# 3PDT_2FX.net
KiCad netlist of a schematic drawn in EAGLE
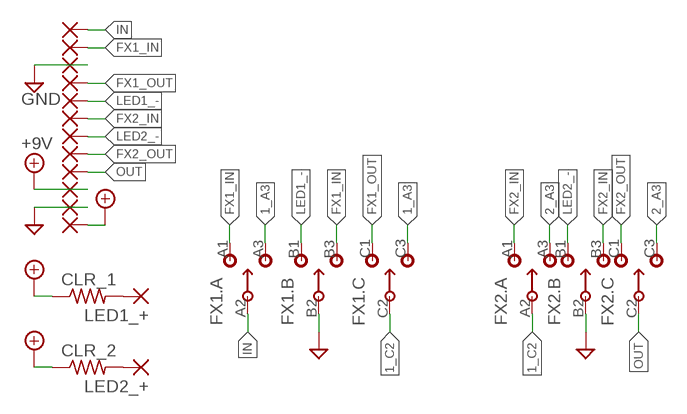
[diagram p0: schematic, sheet 1]

(export (version "E")
  (design (tool "Eeschema 10.0.6"))
  (components
    (comp (ref "+9V")
      (value "1,6/0,8")
      (footprint "eagle-import:1,6_0,8")
      (libsource (lib "eagle-import") (part "1,6/0,8"))
    )
    (comp (ref "+9V1")
      (value "1,6/0,8")
      (footprint "eagle-import:1,6_0,8")
      (libsource (lib "eagle-import") (part "1,6/0,8"))
    )
    (comp (ref "CLR_1")
      (value "R-US_R0603")
      (footprint "eagle-import:R0603")
      (libsource (lib "eagle-import") (part "R-US_R0603"))
    )
    (comp (ref "CLR_2")
      (value "R-US_R0603")
      (footprint "eagle-import:R0603")
      (libsource (lib "eagle-import") (part "R-US_R0603"))
    )
    (comp (ref "FX1")
      (value "3PDT.LUGS")
      (footprint "eagle-import:3PDT.LUGS")
      (libsource (lib "eagle-import") (part "3PDT.LUGS"))
    )
    (comp (ref "FX1_IN")
      (value "1,6/0,8")
      (footprint "eagle-import:1,6_0,8")
      (libsource (lib "eagle-import") (part "1,6/0,8"))
    )
    (comp (ref "FX1_OUT")
      (value "1,6/0,8")
      (footprint "eagle-import:1,6_0,8")
      (libsource (lib "eagle-import") (part "1,6/0,8"))
    )
    (comp (ref "FX2")
      (value "3PDT.LUGS")
      (footprint "eagle-import:3PDT.LUGS")
      (libsource (lib "eagle-import") (part "3PDT.LUGS"))
    )
    (comp (ref "FX2_IN")
      (value "1,6/0,8")
      (footprint "eagle-import:1,6_0,8")
      (libsource (lib "eagle-import") (part "1,6/0,8"))
    )
    (comp (ref "FX2_OUT")
      (value "1,6/0,8")
      (footprint "eagle-import:1,6_0,8")
      (libsource (lib "eagle-import") (part "1,6/0,8"))
    )
    (comp (ref "GND")
      (value "1,6/0,8")
      (footprint "eagle-import:1,6_0,8")
      (libsource (lib "eagle-import") (part "1,6/0,8"))
    )
    (comp (ref "IN")
      (value "1,6/0,8")
      (footprint "eagle-import:1,6_0,8")
      (libsource (lib "eagle-import") (part "1,6/0,8"))
    )
    (comp (ref "LED1_+")
      (value "1,6/0,8")
      (footprint "eagle-import:1,6_0,8")
      (libsource (lib "eagle-import") (part "1,6/0,8"))
    )
    (comp (ref "LED1_-")
      (value "1,6/0,8")
      (footprint "eagle-import:1,6_0,8")
      (libsource (lib "eagle-import") (part "1,6/0,8"))
    )
    (comp (ref "LED2_+")
      (value "1,6/0,8")
      (footprint "eagle-import:1,6_0,8")
      (libsource (lib "eagle-import") (part "1,6/0,8"))
    )
    (comp (ref "LED2_-")
      (value "1,6/0,8")
      (footprint "eagle-import:1,6_0,8")
      (libsource (lib "eagle-import") (part "1,6/0,8"))
    )
    (comp (ref "OUT")
      (value "1,6/0,8")
      (footprint "eagle-import:1,6_0,8")
      (libsource (lib "eagle-import") (part "1,6/0,8"))
    )
    (comp (ref "PAD3")
      (value "1,6/0,8")
      (footprint "eagle-import:1,6_0,8")
      (libsource (lib "eagle-import") (part "1,6/0,8"))
    )
  )
  (nets
    (net (code "1") (name "+9V") (class "Default")
      (node (ref "+9V") (pin "1") (pinfunction "P_1") (pintype "passive"))
      (node (ref "+9V1") (pin "1") (pinfunction "P_1") (pintype "passive"))
      (node (ref "CLR_1") (pin "1") (pinfunction "1_1") (pintype "passive"))
      (node (ref "CLR_2") (pin "1") (pinfunction "1_1") (pintype "passive"))
    )
    (net (code "2") (name "1_A3") (class "Default")
      (node (ref "FX1") (pin "A3") (pinfunction "3_A3") (pintype "passive"))
      (node (ref "FX1") (pin "C3") (pinfunction "3_C3") (pintype "passive"))
    )
    (net (code "3") (name "1_C2") (class "Default")
      (node (ref "FX1") (pin "C2") (pinfunction "2_C2") (pintype "passive"))
      (node (ref "FX2") (pin "A2") (pinfunction "2_A2") (pintype "passive"))
    )
    (net (code "4") (name "2_A3") (class "Default")
      (node (ref "FX2") (pin "A3") (pinfunction "3_A3") (pintype "passive"))
      (node (ref "FX2") (pin "C3") (pinfunction "3_C3") (pintype "passive"))
    )
    (net (code "5") (name "FX1_IN") (class "Default")
      (node (ref "FX1") (pin "A1") (pinfunction "1_A1") (pintype "passive"))
      (node (ref "FX1") (pin "B3") (pinfunction "3_B3") (pintype "passive"))
      (node (ref "FX1_IN") (pin "1") (pinfunction "P_1") (pintype "passive"))
    )
    (net (code "6") (name "FX1_OUT") (class "Default")
      (node (ref "FX1") (pin "C1") (pinfunction "1_C1") (pintype "passive"))
      (node (ref "FX1_OUT") (pin "1") (pinfunction "P_1") (pintype "passive"))
    )
    (net (code "7") (name "FX2_IN") (class "Default")
      (node (ref "FX2") (pin "A1") (pinfunction "1_A1") (pintype "passive"))
      (node (ref "FX2") (pin "B3") (pinfunction "3_B3") (pintype "passive"))
      (node (ref "FX2_IN") (pin "1") (pinfunction "P_1") (pintype "passive"))
    )
    (net (code "8") (name "FX2_OUT") (class "Default")
      (node (ref "FX2") (pin "C1") (pinfunction "1_C1") (pintype "passive"))
      (node (ref "FX2_OUT") (pin "1") (pinfunction "P_1") (pintype "passive"))
    )
    (net (code "9") (name "GND") (class "Default")
      (node (ref "FX1") (pin "B2") (pinfunction "2_B2") (pintype "passive"))
      (node (ref "FX2") (pin "B2") (pinfunction "2_B2") (pintype "passive"))
      (node (ref "GND") (pin "1") (pinfunction "P_1") (pintype "passive"))
      (node (ref "PAD3") (pin "1") (pinfunction "P_1") (pintype "passive"))
    )
    (net (code "10") (name "IN") (class "Default")
      (node (ref "FX1") (pin "A2") (pinfunction "2_A2") (pintype "passive"))
      (node (ref "IN") (pin "1") (pinfunction "P_1") (pintype "passive"))
    )
    (net (code "11") (name "LED1_-") (class "Default")
      (node (ref "FX1") (pin "B1") (pinfunction "1_B1") (pintype "passive"))
      (node (ref "LED1_-") (pin "1") (pinfunction "P_1") (pintype "passive"))
    )
    (net (code "12") (name "LED2_-") (class "Default")
      (node (ref "FX2") (pin "B1") (pinfunction "1_B1") (pintype "passive"))
      (node (ref "LED2_-") (pin "1") (pinfunction "P_1") (pintype "passive"))
    )
    (net (code "13") (name "Net-(LED1_+-P)") (class "Default")
      (node (ref "CLR_1") (pin "2") (pinfunction "2_2") (pintype "passive"))
      (node (ref "LED1_+") (pin "1") (pinfunction "P_1") (pintype "passive"))
    )
    (net (code "14") (name "Net-(LED2_+-P)") (class "Default")
      (node (ref "CLR_2") (pin "2") (pinfunction "2_2") (pintype "passive"))
      (node (ref "LED2_+") (pin "1") (pinfunction "P_1") (pintype "passive"))
    )
    (net (code "15") (name "OUT") (class "Default")
      (node (ref "FX2") (pin "C2") (pinfunction "2_C2") (pintype "passive"))
      (node (ref "OUT") (pin "1") (pinfunction "P_1") (pintype "passive"))
    )
  )
)
